# SH6_-_3_3V_LINEAR_REGULATOR.net
KiCad netlist of a schematic drawn in Altium Designer
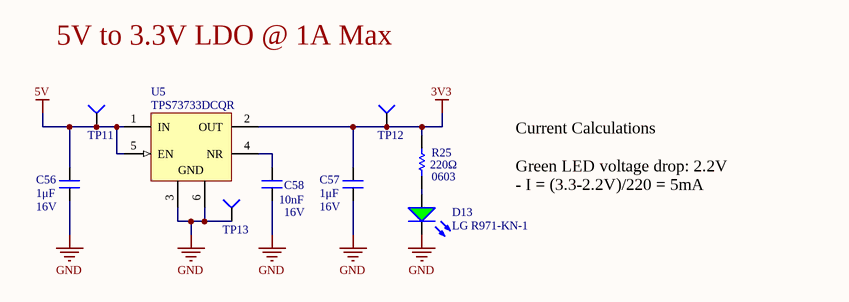
[diagram p0: SH6 - 3.3V LINEAR REGULATOR.SchDoc]

(export (version "E")
  (design (tool "Eeschema 10.0.6"))
  (components
    (comp (ref "C56")
      (value "1μF")
      (footprint "CAP0603")
      (description "CAP CER 1UF 16V Y5V 0603")
      (fields
        (field (name "VOLTAGE RATING") "16V")
        (field (name "MANUFACTURER PART NUMBER") "CC0603ZRY5V7BB105")
        (field (name "Comment") "CAP_1uF_16V_0603")
      )
      (libsource (lib "UWRT_Schematic_Library_2020") (part "CAP_1uF_16V_0603"))
    )
    (comp (ref "C57")
      (value "1μF")
      (footprint "CAP0603")
      (description "CAP CER 1UF 16V Y5V 0603")
      (fields
        (field (name "VOLTAGE RATING") "16V")
        (field (name "MANUFACTURER PART NUMBER") "CC0603ZRY5V7BB105")
        (field (name "Comment") "CAP_1uF_16V_0603")
      )
      (libsource (lib "UWRT_Schematic_Library_2020") (part "CAP_1uF_16V_0603"))
    )
    (comp (ref "C58")
      (value "10nF")
      (footprint "CAP0603")
      (description "CAP CER 10000PF 16V X7R 0603")
      (fields (field (name "VOLTAGE RATING") "16V") (field (name "Comment") "CAP_10nF_0603"))
      (libsource (lib "UWRT_Schematic_Library_2020") (part "CAP_10nF_0603"))
    )
    (comp (ref "D13")
      (value "LG R971-KN-1")
      (footprint "LED_0805_GREEN")
      (description "LED GREEN DIFFUSED 0805 SMD")
      (libsource (lib "UWRT_Schematic_Library_2020") (part "DIO_LED_G"))
    )
    (comp (ref "R25")
      (value "220Ω")
      (footprint "RESC0603(1608)_N")
      (description "RES 220 OHM 5% 1/10W 0603")
      (fields
        (field (name "TOLERANCE") "5%")
        (field (name "CASE CODE (IMPERIAL)") "0603")
        (field (name "Comment") "RES_220Ω_0603")
      )
      (libsource (lib "UWRT_Schematic_Library_2020") (part "RES_220Ω_0603_5%"))
    )
    (comp (ref "TP11")
      (value "TESTPOINT_SMD_LOOP")
      (footprint "S1751-46R")
      (description "PC TEST POINT SMD")
      (libsource (lib "UWRT_Schematic_Library_2020") (part "TESTPOINT_SMD_LOOP"))
    )
    (comp (ref "TP12")
      (value "TESTPOINT_SMD_LOOP")
      (footprint "S1751-46R")
      (description "PC TEST POINT SMD")
      (libsource (lib "UWRT_Schematic_Library_2020") (part "TESTPOINT_SMD_LOOP"))
    )
    (comp (ref "TP13")
      (value "TESTPOINT_SMD_LOOP")
      (footprint "S1751-46R")
      (description "PC TEST POINT SMD")
      (libsource (lib "UWRT_Schematic_Library_2020") (part "TESTPOINT_SMD_LOOP"))
    )
    (comp (ref "U5")
      (value "TPS73733DCQR")
      (footprint "UWRT_Footprint_Library_2020:SOT-223-6")
      (description "IC REG LINEAR 3.3V 1A SOT223-6")
      (fields (field (name "MANUFACTURER") "Texas Instruments"))
      (libsource (lib "UWRT_Schematic_Library_2020") (part "LDO_3.3V_1A"))
    )
  )
  (nets
    (net (code "1") (name "3V3") (class "Default")
      (node (ref "C57") (pin "2") (pinfunction "2_2") (pintype "passive"))
      (node (ref "R25") (pin "2") (pinfunction "2_2") (pintype "passive"))
      (node (ref "TP12") (pin "1") (pinfunction "=value_1") (pintype "passive"))
      (node (ref "U5") (pin "2") (pinfunction "OUT_2") (pintype "power_in"))
    )
    (net (code "2") (name "5V") (class "Default")
      (node (ref "C56") (pin "2") (pinfunction "2_2") (pintype "passive"))
      (node (ref "TP11") (pin "1") (pinfunction "=value_1") (pintype "passive"))
      (node (ref "U5") (pin "1") (pinfunction "IN_1") (pintype "power_in"))
      (node (ref "U5") (pin "5") (pinfunction "EN_5") (pintype "input"))
    )
    (net (code "3") (name "GND") (class "Default")
      (node (ref "C56") (pin "1") (pinfunction "1_1") (pintype "passive"))
      (node (ref "C57") (pin "1") (pinfunction "1_1") (pintype "passive"))
      (node (ref "C58") (pin "1") (pinfunction "1_1") (pintype "passive"))
      (node (ref "D13") (pin "2") (pinfunction "K_2") (pintype "passive"))
      (node (ref "TP13") (pin "1") (pinfunction "=value_1") (pintype "passive"))
      (node (ref "U5") (pin "3") (pinfunction "GND_3") (pintype "power_in"))
      (node (ref "U5") (pin "6") (pinfunction "GND_6") (pintype "power_in"))
    )
    (net (code "4") (name "Net-(D13-A)") (class "Default")
      (node (ref "D13") (pin "1") (pinfunction "A_1") (pintype "passive"))
      (node (ref "R25") (pin "1") (pinfunction "1_1") (pintype "passive"))
    )
    (net (code "5") (name "Net-(U5-NR)") (class "Default")
      (node (ref "C58") (pin "2") (pinfunction "2_2") (pintype "passive"))
      (node (ref "U5") (pin "4") (pinfunction "NR_4") (pintype "passive"))
    )
  )
)
